# PIC32.net
KiCad netlist of a schematic drawn in Altium Designer
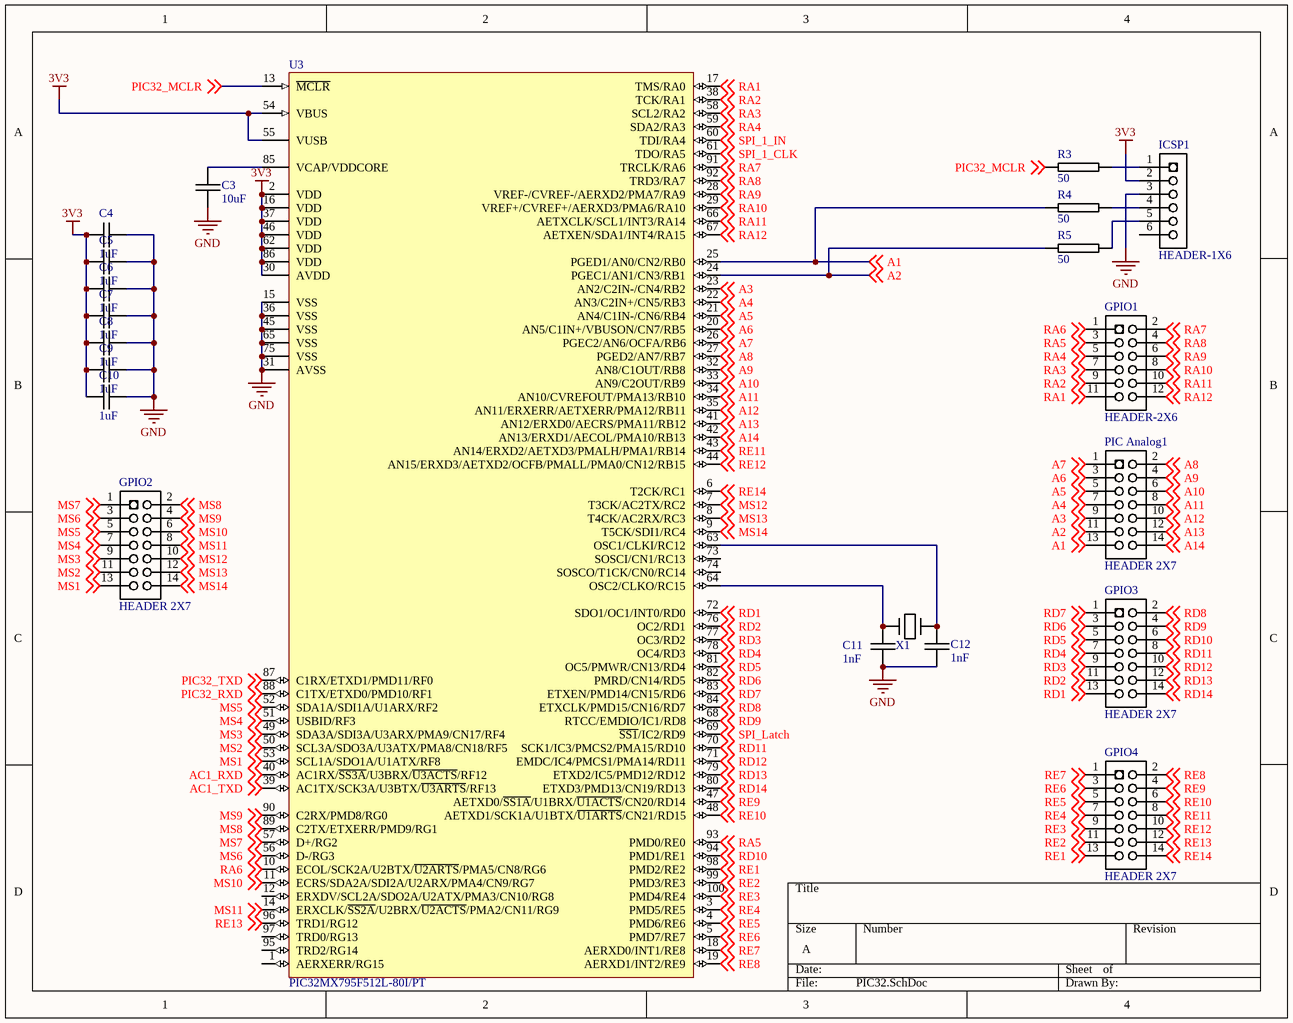
[diagram p0: PIC32.SchDoc]

(export (version "E")
  (design (tool "Eeschema 10.0.6"))
  (components
    (comp (ref "C3")
      (value "10uF")
      (footprint "0603C-GENERIC")
      (description "CAPACITOR 0603 CERAMIC")
      (fields
        (field (name "MANUFACTURER PART NUMBER") "GMK107BJ105KA-T")
        (field (name "MANUFACTURER") "Taiyo Yuden")
      )
      (libsource (lib "vh_altium_library") (part "0603C-1UF-35V-X5R-TAY"))
    )
    (comp (ref "C4")
      (value "1uF")
      (footprint "0603C-GENERIC")
      (description "CAPACITOR 0603 CERAMIC")
      (fields
        (field (name "MANUFACTURER PART NUMBER") "GMK107BJ105KA-T")
        (field (name "MANUFACTURER") "Taiyo Yuden")
      )
      (libsource (lib "vh_altium_library") (part "0603C-1UF-35V-X5R-TAY"))
    )
    (comp (ref "C5")
      (value "1uF")
      (footprint "0603C-GENERIC")
      (description "CAPACITOR 0603 CERAMIC")
      (fields
        (field (name "MANUFACTURER PART NUMBER") "GMK107BJ105KA-T")
        (field (name "MANUFACTURER") "Taiyo Yuden")
      )
      (libsource (lib "vh_altium_library") (part "0603C-1UF-35V-X5R-TAY"))
    )
    (comp (ref "C6")
      (value "1uF")
      (footprint "0603C-GENERIC")
      (description "CAPACITOR 0603 CERAMIC")
      (fields
        (field (name "MANUFACTURER PART NUMBER") "GMK107BJ105KA-T")
        (field (name "MANUFACTURER") "Taiyo Yuden")
      )
      (libsource (lib "vh_altium_library") (part "0603C-1UF-35V-X5R-TAY"))
    )
    (comp (ref "C7")
      (value "1uF")
      (footprint "0603C-GENERIC")
      (description "CAPACITOR 0603 CERAMIC")
      (fields
        (field (name "MANUFACTURER PART NUMBER") "GMK107BJ105KA-T")
        (field (name "MANUFACTURER") "Taiyo Yuden")
      )
      (libsource (lib "vh_altium_library") (part "0603C-1UF-35V-X5R-TAY"))
    )
    (comp (ref "C8")
      (value "1uF")
      (footprint "0603C-GENERIC")
      (description "CAPACITOR 0603 CERAMIC")
      (fields
        (field (name "MANUFACTURER PART NUMBER") "GMK107BJ105KA-T")
        (field (name "MANUFACTURER") "Taiyo Yuden")
      )
      (libsource (lib "vh_altium_library") (part "0603C-1UF-35V-X5R-TAY"))
    )
    (comp (ref "C9")
      (value "1uF")
      (footprint "0603C-GENERIC")
      (description "CAPACITOR 0603 CERAMIC")
      (fields
        (field (name "MANUFACTURER PART NUMBER") "GMK107BJ105KA-T")
        (field (name "MANUFACTURER") "Taiyo Yuden")
      )
      (libsource (lib "vh_altium_library") (part "0603C-1UF-35V-X5R-TAY"))
    )
    (comp (ref "C10")
      (value "1uF")
      (footprint "0603C-GENERIC")
      (description "CAPACITOR 0603 CERAMIC")
      (fields
        (field (name "MANUFACTURER PART NUMBER") "GMK107BJ105KA-T")
        (field (name "MANUFACTURER") "Taiyo Yuden")
      )
      (libsource (lib "vh_altium_library") (part "0603C-1UF-35V-X5R-TAY"))
    )
    (comp (ref "C11")
      (value "1nF")
      (footprint "0603C-GENERIC")
      (description "CAPACITOR 0603 CERAMIC")
      (libsource (lib "vh_altium_library") (part "0603C-000"))
    )
    (comp (ref "C12")
      (value "1nF")
      (footprint "0603C-GENERIC")
      (description "CAPACITOR 0603 CERAMIC")
      (libsource (lib "vh_altium_library") (part "0603C-000"))
    )
    (comp (ref "GPIO1")
      (value "HEADER-2X6")
      (footprint "HEADER-2X6")
      (libsource (lib "vh_altium_library") (part "HEADER-2X6"))
    )
    (comp (ref "GPIO2")
      (value "HEADER 2X7")
      (footprint "HEADER-2X7")
      (libsource (lib "vh_altium_library") (part "HEADER-2X7"))
    )
    (comp (ref "GPIO3")
      (value "HEADER 2X7")
      (footprint "HEADER-2X7")
      (libsource (lib "vh_altium_library") (part "HEADER-2X7"))
    )
    (comp (ref "GPIO4")
      (value "HEADER 2X7")
      (footprint "HEADER-2X7")
      (libsource (lib "vh_altium_library") (part "HEADER-2X7"))
    )
    (comp (ref "ICSP1")
      (value "HEADER-1X6")
      (footprint "HEADER-1X6")
      (libsource (lib "vh_altium_library") (part "HEADER-1X6"))
    )
    (comp (ref "PIC Analog1")
      (value "HEADER 2X7")
      (footprint "HEADER-2X7")
      (libsource (lib "vh_altium_library") (part "HEADER-2X7"))
    )
    (comp (ref "R3")
      (value "50")
      (footprint "0603R-TBD")
      (description "RESISTOR 0603 VALUE TO BE DETERMINED")
      (libsource (lib "vh_altium_library") (part "0603R-TBD"))
    )
    (comp (ref "R4")
      (value "50")
      (footprint "0603R-TBD")
      (description "RESISTOR 0603 VALUE TO BE DETERMINED")
      (libsource (lib "vh_altium_library") (part "0603R-TBD"))
    )
    (comp (ref "R5")
      (value "50")
      (footprint "0603R-TBD")
      (description "RESISTOR 0603 VALUE TO BE DETERMINED")
      (libsource (lib "vh_altium_library") (part "0603R-TBD"))
    )
    (comp (ref "U3")
      (value "PIC32MX795F512L-80I/PT")
      (footprint "TQFP-PT100_N")
      (fields (field (name "PUBLISHER") "Altium Limited"))
      (libsource (lib "Microchip Microcontroller 32-Bit PIC32") (part "PIC32MX795F512L-80I/PT"))
    )
    (comp (ref "X1")
      (value "CRYSTAL-GENERIC")
      (footprint "XTAL-RU49/4")
      (description "GENERIC CRYSTAL")
      (libsource (lib "vh_altium_library") (part "CRYSTAL-GENERIC"))
    )
  )
  (nets
    (net (code "1") (name "3V3") (class "Default")
      (node (ref "C10") (pin "1") (pintype "passive"))
      (node (ref "C4") (pin "1") (pintype "passive"))
      (node (ref "C5") (pin "1") (pintype "passive"))
      (node (ref "C6") (pin "1") (pintype "passive"))
      (node (ref "C7") (pin "1") (pintype "passive"))
      (node (ref "C8") (pin "1") (pintype "passive"))
      (node (ref "C9") (pin "1") (pintype "passive"))
      (node (ref "ICSP1") (pin "2") (pintype "passive"))
      (node (ref "U3") (pin "16") (pinfunction "VDD_16") (pintype "power_in"))
      (node (ref "U3") (pin "2") (pinfunction "VDD_2") (pintype "power_in"))
      (node (ref "U3") (pin "30") (pinfunction "AVDD_30") (pintype "power_in"))
      (node (ref "U3") (pin "37") (pinfunction "VDD_37") (pintype "power_in"))
      (node (ref "U3") (pin "46") (pinfunction "VDD_46") (pintype "power_in"))
      (node (ref "U3") (pin "54") (pinfunction "VBUS_54") (pintype "input"))
      (node (ref "U3") (pin "55") (pinfunction "VUSB_55") (pintype "power_in"))
      (node (ref "U3") (pin "62") (pinfunction "VDD_62") (pintype "power_in"))
      (node (ref "U3") (pin "86") (pinfunction "VDD_86") (pintype "power_in"))
    )
    (net (code "2") (name "A1") (class "Default")
      (node (ref "PIC Analog1") (pin "13") (pintype "passive"))
      (node (ref "R4") (pin "1") (pintype "passive"))
      (node (ref "U3") (pin "25") (pinfunction "PGED1/AN0/CN2/RB0_25") (pintype "bidirectional"))
    )
    (net (code "3") (name "A2") (class "Default")
      (node (ref "PIC Analog1") (pin "11") (pintype "passive"))
      (node (ref "R5") (pin "2") (pintype "passive"))
      (node (ref "U3") (pin "24") (pinfunction "PGEC1/AN1/CN3/RB1_24") (pintype "bidirectional"))
    )
    (net (code "4") (name "A3") (class "Default")
      (node (ref "PIC Analog1") (pin "9") (pintype "passive"))
      (node (ref "U3") (pin "23") (pinfunction "AN2/C2IN-/CN4/RB2_23") (pintype "bidirectional"))
    )
    (net (code "5") (name "A4") (class "Default")
      (node (ref "PIC Analog1") (pin "7") (pintype "passive"))
      (node (ref "U3") (pin "22") (pinfunction "AN3/C2IN+/CN5/RB3_22") (pintype "bidirectional"))
    )
    (net (code "6") (name "A5") (class "Default")
      (node (ref "PIC Analog1") (pin "5") (pintype "passive"))
      (node (ref "U3") (pin "21") (pinfunction "AN4/C1IN-/CN6/RB4_21") (pintype "bidirectional"))
    )
    (net (code "7") (name "A6") (class "Default")
      (node (ref "PIC Analog1") (pin "3") (pintype "passive"))
      (node (ref "U3") (pin "20") (pinfunction "AN5/C1IN+/VBUSON/CN7/RB5_20") (pintype "bidirectional"))
    )
    (net (code "8") (name "A7") (class "Default")
      (node (ref "PIC Analog1") (pin "1") (pintype "passive"))
      (node (ref "U3") (pin "26") (pinfunction "PGEC2/AN6/OCFA/RB6_26") (pintype "bidirectional"))
    )
    (net (code "9") (name "A8") (class "Default")
      (node (ref "PIC Analog1") (pin "2") (pintype "passive"))
      (node (ref "U3") (pin "27") (pinfunction "PGED2/AN7/RB7_27") (pintype "bidirectional"))
    )
    (net (code "10") (name "A9") (class "Default")
      (node (ref "PIC Analog1") (pin "4") (pintype "passive"))
      (node (ref "U3") (pin "32") (pinfunction "AN8/C1OUT/RB8_32") (pintype "bidirectional"))
    )
    (net (code "11") (name "A10") (class "Default")
      (node (ref "PIC Analog1") (pin "6") (pintype "passive"))
      (node (ref "U3") (pin "33") (pinfunction "AN9/C2OUT/RB9_33") (pintype "bidirectional"))
    )
    (net (code "12") (name "A11") (class "Default")
      (node (ref "PIC Analog1") (pin "8") (pintype "passive"))
      (node (ref "U3") (pin "34") (pinfunction "AN10/CVREFOUT/PMA13/RB10_34") (pintype "bidirectional"))
    )
    (net (code "13") (name "A12") (class "Default")
      (node (ref "PIC Analog1") (pin "10") (pintype "passive"))
      (node (ref "U3") (pin "35") (pinfunction "AN11/ERXERR/AETXERR/PMA12/RB11_35") (pintype "bidirectional"))
    )
    (net (code "14") (name "A13") (class "Default")
      (node (ref "PIC Analog1") (pin "12") (pintype "passive"))
      (node (ref "U3") (pin "41") (pinfunction "AN12/ERXD0/AECRS/PMA11/RB12_41") (pintype "bidirectional"))
    )
    (net (code "15") (name "A14") (class "Default")
      (node (ref "PIC Analog1") (pin "14") (pintype "passive"))
      (node (ref "U3") (pin "42") (pinfunction "AN13/ERXD1/AECOL/PMA10/RB13_42") (pintype "bidirectional"))
    )
    (net (code "16") (name "AC1_RXD") (class "Default")
      (node (ref "U3") (pin "40") (pinfunction "AC1RX/~{SS3A}/U3BRX/~{U3ACTS}/RF12_40") (pintype "bidirectional"))
    )
    (net (code "17") (name "AC1_TXD") (class "Default")
      (node (ref "U3") (pin "39") (pinfunction "AC1TX/SCK3A/U3BTX/~{U3ARTS}/RF13_39") (pintype "bidirectional"))
    )
    (net (code "18") (name "GND") (class "Default")
      (node (ref "C10") (pin "2") (pintype "passive"))
      (node (ref "C11") (pin "2") (pintype "passive"))
      (node (ref "C12") (pin "2") (pintype "passive"))
      (node (ref "C3") (pin "2") (pintype "passive"))
      (node (ref "C4") (pin "2") (pintype "passive"))
      (node (ref "C5") (pin "2") (pintype "passive"))
      (node (ref "C6") (pin "2") (pintype "passive"))
      (node (ref "C7") (pin "2") (pintype "passive"))
      (node (ref "C8") (pin "2") (pintype "passive"))
      (node (ref "C9") (pin "2") (pintype "passive"))
      (node (ref "ICSP1") (pin "3") (pintype "passive"))
      (node (ref "U3") (pin "15") (pinfunction "VSS_15") (pintype "power_in"))
      (node (ref "U3") (pin "31") (pinfunction "AVSS_31") (pintype "power_in"))
      (node (ref "U3") (pin "36") (pinfunction "VSS_36") (pintype "power_in"))
      (node (ref "U3") (pin "45") (pinfunction "VSS_45") (pintype "power_in"))
      (node (ref "U3") (pin "65") (pinfunction "VSS_65") (pintype "power_in"))
      (node (ref "U3") (pin "75") (pinfunction "VSS_75") (pintype "power_in"))
    )
    (net (code "19") (name "MS1") (class "Default")
      (node (ref "GPIO2") (pin "13") (pintype "passive"))
      (node (ref "U3") (pin "53") (pinfunction "SCL1A/SDO1A/U1ATX/RF8_53") (pintype "bidirectional"))
    )
    (net (code "20") (name "MS2") (class "Default")
      (node (ref "GPIO2") (pin "11") (pintype "passive"))
      (node (ref "U3") (pin "50") (pinfunction "SCL3A/SDO3A/U3ATX/PMA8/CN18/RF5_50") (pintype "bidirectional"))
    )
    (net (code "21") (name "MS3") (class "Default")
      (node (ref "GPIO2") (pin "9") (pintype "passive"))
      (node (ref "U3") (pin "49") (pinfunction "SDA3A/SDI3A/U3ARX/PMA9/CN17/RF4_49") (pintype "bidirectional"))
    )
    (net (code "22") (name "MS4") (class "Default")
      (node (ref "GPIO2") (pin "7") (pintype "passive"))
      (node (ref "U3") (pin "51") (pinfunction "USBID/RF3_51") (pintype "bidirectional"))
    )
    (net (code "23") (name "MS5") (class "Default")
      (node (ref "GPIO2") (pin "5") (pintype "passive"))
      (node (ref "U3") (pin "52") (pinfunction "SDA1A/SDI1A/U1ARX/RF2_52") (pintype "bidirectional"))
    )
    (net (code "24") (name "MS6") (class "Default")
      (node (ref "GPIO2") (pin "3") (pintype "passive"))
      (node (ref "U3") (pin "56") (pinfunction "D-/RG3_56") (pintype "bidirectional"))
    )
    (net (code "25") (name "MS7") (class "Default")
      (node (ref "GPIO2") (pin "1") (pintype "passive"))
      (node (ref "U3") (pin "57") (pinfunction "D+/RG2_57") (pintype "bidirectional"))
    )
    (net (code "26") (name "MS8") (class "Default")
      (node (ref "GPIO2") (pin "2") (pintype "passive"))
      (node (ref "U3") (pin "89") (pinfunction "C2TX/ETXERR/PMD9/RG1_89") (pintype "bidirectional"))
    )
    (net (code "27") (name "MS9") (class "Default")
      (node (ref "GPIO2") (pin "4") (pintype "passive"))
      (node (ref "U3") (pin "90") (pinfunction "C2RX/PMD8/RG0_90") (pintype "bidirectional"))
    )
    (net (code "28") (name "MS10") (class "Default")
      (node (ref "GPIO2") (pin "6") (pintype "passive"))
      (node (ref "U3") (pin "11") (pinfunction "ECRS/SDA2A/SDI2A/U2ARX/PMA4/CN9/RG7_11") (pintype "bidirectional"))
    )
    (net (code "29") (name "MS11") (class "Default")
      (node (ref "GPIO2") (pin "8") (pintype "passive"))
      (node (ref "U3") (pin "14") (pinfunction "ERXCLK/~{SS2A}/U2BRX/~{U2ACTS}/PMA2/CN11/RG9_14") (pintype "bidirectional"))
    )
    (net (code "30") (name "MS12") (class "Default")
      (node (ref "GPIO2") (pin "10") (pintype "passive"))
      (node (ref "U3") (pin "7") (pinfunction "T3CK/AC2TX/RC2_7") (pintype "bidirectional"))
    )
    (net (code "31") (name "MS13") (class "Default")
      (node (ref "GPIO2") (pin "12") (pintype "passive"))
      (node (ref "U3") (pin "8") (pinfunction "T4CK/AC2RX/RC3_8") (pintype "bidirectional"))
    )
    (net (code "32") (name "MS14") (class "Default")
      (node (ref "GPIO2") (pin "14") (pintype "passive"))
      (node (ref "U3") (pin "9") (pinfunction "T5CK/SDI1/RC4_9") (pintype "bidirectional"))
    )
    (net (code "33") (name "Net-(ICSP1-Pad1)") (class "Default")
      (node (ref "ICSP1") (pin "1") (pintype "passive"))
      (node (ref "R3") (pin "1") (pintype "passive"))
    )
    (net (code "34") (name "Net-(ICSP1-Pad4)") (class "Default")
      (node (ref "ICSP1") (pin "4") (pintype "passive"))
      (node (ref "R4") (pin "2") (pintype "passive"))
    )
    (net (code "35") (name "Net-(ICSP1-Pad5)") (class "Default")
      (node (ref "ICSP1") (pin "5") (pintype "passive"))
      (node (ref "R5") (pin "1") (pintype "passive"))
    )
    (net (code "36") (name "Net-(U3-OSC1{slash}CLKI{slash}RC12)") (class "Default")
      (node (ref "C12") (pin "1") (pintype "passive"))
      (node (ref "U3") (pin "63") (pinfunction "OSC1/CLKI/RC12_63") (pintype "bidirectional"))
      (node (ref "X1") (pin "2") (pintype "passive"))
    )
    (net (code "37") (name "Net-(U3-OSC2{slash}CLKO{slash}RC15)") (class "Default")
      (node (ref "C11") (pin "1") (pintype "passive"))
      (node (ref "U3") (pin "64") (pinfunction "OSC2/CLKO/RC15_64") (pintype "bidirectional"))
      (node (ref "X1") (pin "1") (pintype "passive"))
    )
    (net (code "38") (name "Net-(U3-VCAP{slash}VDDCORE)") (class "Default")
      (node (ref "C3") (pin "1") (pintype "passive"))
      (node (ref "U3") (pin "85") (pinfunction "VCAP/VDDCORE_85") (pintype "power_in"))
    )
    (net (code "39") (name "PIC32_MCLR") (class "Default")
      (node (ref "R3") (pin "2") (pintype "passive"))
      (node (ref "U3") (pin "13") (pinfunction "~{MCLR}_13") (pintype "input"))
    )
    (net (code "40") (name "PIC32_RXD") (class "Default")
      (node (ref "U3") (pin "88") (pinfunction "C1TX/ETXD0/PMD10/RF1_88") (pintype "bidirectional"))
    )
    (net (code "41") (name "PIC32_TXD") (class "Default")
      (node (ref "U3") (pin "87") (pinfunction "C1RX/ETXD1/PMD11/RF0_87") (pintype "bidirectional"))
    )
    (net (code "42") (name "RA1") (class "Default")
      (node (ref "GPIO1") (pin "11") (pintype "passive"))
      (node (ref "U3") (pin "17") (pinfunction "TMS/RA0_17") (pintype "bidirectional"))
    )
    (net (code "43") (name "RA2") (class "Default")
      (node (ref "GPIO1") (pin "9") (pintype "passive"))
      (node (ref "U3") (pin "38") (pinfunction "TCK/RA1_38") (pintype "bidirectional"))
    )
    (net (code "44") (name "RA3") (class "Default")
      (node (ref "GPIO1") (pin "7") (pintype "passive"))
      (node (ref "U3") (pin "58") (pinfunction "SCL2/RA2_58") (pintype "bidirectional"))
    )
    (net (code "45") (name "RA4") (class "Default")
      (node (ref "GPIO1") (pin "5") (pintype "passive"))
      (node (ref "U3") (pin "59") (pinfunction "SDA2/RA3_59") (pintype "bidirectional"))
    )
    (net (code "46") (name "RA5") (class "Default")
      (node (ref "GPIO1") (pin "3") (pintype "passive"))
      (node (ref "U3") (pin "93") (pinfunction "PMD0/RE0_93") (pintype "bidirectional"))
    )
    (net (code "47") (name "RA6") (class "Default")
      (node (ref "GPIO1") (pin "1") (pintype "passive"))
      (node (ref "U3") (pin "10") (pinfunction "ECOL/SCK2A/U2BTX/~{U2ARTS}/PMA5/CN8/RG6_10") (pintype "bidirectional"))
    )
    (net (code "48") (name "RA7") (class "Default")
      (node (ref "GPIO1") (pin "2") (pintype "passive"))
      (node (ref "U3") (pin "91") (pinfunction "TRCLK/RA6_91") (pintype "bidirectional"))
    )
    (net (code "49") (name "RA8") (class "Default")
      (node (ref "GPIO1") (pin "4") (pintype "passive"))
      (node (ref "U3") (pin "92") (pinfunction "TRD3/RA7_92") (pintype "bidirectional"))
    )
    (net (code "50") (name "RA9") (class "Default")
      (node (ref "GPIO1") (pin "6") (pintype "passive"))
      (node (ref "U3") (pin "28") (pinfunction "VREF-/CVREF-/AERXD2/PMA7/RA9_28") (pintype "bidirectional"))
    )
    (net (code "51") (name "RA10") (class "Default")
      (node (ref "GPIO1") (pin "8") (pintype "passive"))
      (node (ref "U3") (pin "29") (pinfunction "VREF+/CVREF+/AERXD3/PMA6/RA10_29") (pintype "bidirectional"))
    )
    (net (code "52") (name "RA11") (class "Default")
      (node (ref "GPIO1") (pin "10") (pintype "passive"))
      (node (ref "U3") (pin "66") (pinfunction "AETXCLK/SCL1/INT3/RA14_66") (pintype "bidirectional"))
    )
    (net (code "53") (name "RA12") (class "Default")
      (node (ref "GPIO1") (pin "12") (pintype "passive"))
      (node (ref "U3") (pin "67") (pinfunction "AETXEN/SDA1/INT4/RA15_67") (pintype "bidirectional"))
    )
    (net (code "54") (name "RD1") (class "Default")
      (node (ref "GPIO3") (pin "13") (pintype "passive"))
      (node (ref "U3") (pin "72") (pinfunction "SDO1/OC1/INT0/RD0_72") (pintype "bidirectional"))
    )
    (net (code "55") (name "RD2") (class "Default")
      (node (ref "GPIO3") (pin "11") (pintype "passive"))
      (node (ref "U3") (pin "76") (pinfunction "OC2/RD1_76") (pintype "bidirectional"))
    )
    (net (code "56") (name "RD3") (class "Default")
      (node (ref "GPIO3") (pin "9") (pintype "passive"))
      (node (ref "U3") (pin "77") (pinfunction "OC3/RD2_77") (pintype "bidirectional"))
    )
    (net (code "57") (name "RD4") (class "Default")
      (node (ref "GPIO3") (pin "7") (pintype "passive"))
      (node (ref "U3") (pin "78") (pinfunction "OC4/RD3_78") (pintype "bidirectional"))
    )
    (net (code "58") (name "RD5") (class "Default")
      (node (ref "GPIO3") (pin "5") (pintype "passive"))
      (node (ref "U3") (pin "81") (pinfunction "OC5/PMWR/CN13/RD4_81") (pintype "bidirectional"))
    )
    (net (code "59") (name "RD6") (class "Default")
      (node (ref "GPIO3") (pin "3") (pintype "passive"))
      (node (ref "U3") (pin "82") (pinfunction "PMRD/CN14/RD5_82") (pintype "bidirectional"))
    )
    (net (code "60") (name "RD7") (class "Default")
      (node (ref "GPIO3") (pin "1") (pintype "passive"))
      (node (ref "U3") (pin "83") (pinfunction "ETXEN/PMD14/CN15/RD6_83") (pintype "bidirectional"))
    )
    (net (code "61") (name "RD8") (class "Default")
      (node (ref "GPIO3") (pin "2") (pintype "passive"))
      (node (ref "U3") (pin "84") (pinfunction "ETXCLK/PMD15/CN16/RD7_84") (pintype "bidirectional"))
    )
    (net (code "62") (name "RD9") (class "Default")
      (node (ref "GPIO3") (pin "4") (pintype "passive"))
      (node (ref "U3") (pin "68") (pinfunction "RTCC/EMDIO/IC1/RD8_68") (pintype "bidirectional"))
    )
    (net (code "63") (name "RD10") (class "Default")
      (node (ref "GPIO3") (pin "6") (pintype "passive"))
      (node (ref "U3") (pin "94") (pinfunction "PMD1/RE1_94") (pintype "bidirectional"))
    )
    (net (code "64") (name "RD11") (class "Default")
      (node (ref "GPIO3") (pin "8") (pintype "passive"))
      (node (ref "U3") (pin "70") (pinfunction "SCK1/IC3/PMCS2/PMA15/RD10_70") (pintype "bidirectional"))
    )
    (net (code "65") (name "RD12") (class "Default")
      (node (ref "GPIO3") (pin "10") (pintype "passive"))
      (node (ref "U3") (pin "71") (pinfunction "EMDC/IC4/PMCS1/PMA14/RD11_71") (pintype "bidirectional"))
    )
    (net (code "66") (name "RD13") (class "Default")
      (node (ref "GPIO3") (pin "12") (pintype "passive"))
      (node (ref "U3") (pin "79") (pinfunction "ETXD2/IC5/PMD12/RD12_79") (pintype "bidirectional"))
    )
    (net (code "67") (name "RD14") (class "Default")
      (node (ref "GPIO3") (pin "14") (pintype "passive"))
      (node (ref "U3") (pin "80") (pinfunction "ETXD3/PMD13/CN19/RD13_80") (pintype "bidirectional"))
    )
    (net (code "68") (name "RE1") (class "Default")
      (node (ref "GPIO4") (pin "13") (pintype "passive"))
      (node (ref "U3") (pin "98") (pinfunction "PMD2/RE2_98") (pintype "bidirectional"))
    )
    (net (code "69") (name "RE2") (class "Default")
      (node (ref "GPIO4") (pin "11") (pintype "passive"))
      (node (ref "U3") (pin "99") (pinfunction "PMD3/RE3_99") (pintype "bidirectional"))
    )
    (net (code "70") (name "RE3") (class "Default")
      (node (ref "GPIO4") (pin "9") (pintype "passive"))
      (node (ref "U3") (pin "100") (pinfunction "PMD4/RE4_100") (pintype "bidirectional"))
    )
    (net (code "71") (name "RE4") (class "Default")
      (node (ref "GPIO4") (pin "7") (pintype "passive"))
      (node (ref "U3") (pin "3") (pinfunction "PMD5/RE5_3") (pintype "bidirectional"))
    )
    (net (code "72") (name "RE5") (class "Default")
      (node (ref "GPIO4") (pin "5") (pintype "passive"))
      (node (ref "U3") (pin "4") (pinfunction "PMD6/RE6_4") (pintype "bidirectional"))
    )
    (net (code "73") (name "RE6") (class "Default")
      (node (ref "GPIO4") (pin "3") (pintype "passive"))
      (node (ref "U3") (pin "5") (pinfunction "PMD7/RE7_5") (pintype "bidirectional"))
    )
    (net (code "74") (name "RE7") (class "Default")
      (node (ref "GPIO4") (pin "1") (pintype "passive"))
      (node (ref "U3") (pin "18") (pinfunction "AERXD0/INT1/RE8_18") (pintype "bidirectional"))
    )
    (net (code "75") (name "RE8") (class "Default")
      (node (ref "GPIO4") (pin "2") (pintype "passive"))
      (node (ref "U3") (pin "19") (pinfunction "AERXD1/INT2/RE9_19") (pintype "bidirectional"))
    )
    (net (code "76") (name "RE9") (class "Default")
      (node (ref "GPIO4") (pin "4") (pintype "passive"))
      (node (ref "U3") (pin "47") (pinfunction "AETXD0/~{SS1A}/U1BRX/~{U1ACTS}/CN20/RD14_47") (pintype "bidirectional"))
    )
    (net (code "77") (name "RE10") (class "Default")
      (node (ref "GPIO4") (pin "6") (pintype "passive"))
      (node (ref "U3") (pin "48") (pinfunction "AETXD1/SCK1A/U1BTX/~{U1ARTS}/CN21/RD15_48") (pintype "bidirectional"))
    )
    (net (code "78") (name "RE11") (class "Default")
      (node (ref "GPIO4") (pin "8") (pintype "passive"))
      (node (ref "U3") (pin "43") (pinfunction "AN14/ERXD2/AETXD3/PMALH/PMA1/RB14_43") (pintype "bidirectional"))
    )
    (net (code "79") (name "RE12") (class "Default")
      (node (ref "GPIO4") (pin "10") (pintype "passive"))
      (node (ref "U3") (pin "44") (pinfunction "AN15/ERXD3/AETXD2/OCFB/PMALL/PMA0/CN12/RB15_44") (pintype "bidirectional"))
    )
    (net (code "80") (name "RE13") (class "Default")
      (node (ref "GPIO4") (pin "12") (pintype "passive"))
      (node (ref "U3") (pin "96") (pinfunction "TRD1/RG12_96") (pintype "bidirectional"))
    )
    (net (code "81") (name "RE14") (class "Default")
      (node (ref "GPIO4") (pin "14") (pintype "passive"))
      (node (ref "U3") (pin "6") (pinfunction "T2CK/RC1_6") (pintype "bidirectional"))
    )
    (net (code "82") (name "SPI_1_CLK") (class "Default")
      (node (ref "U3") (pin "61") (pinfunction "TDO/RA5_61") (pintype "bidirectional"))
    )
    (net (code "83") (name "SPI_1_IN") (class "Default")
      (node (ref "U3") (pin "60") (pinfunction "TDI/RA4_60") (pintype "bidirectional"))
    )
    (net (code "84") (name "SPI_Latch") (class "Default")
      (node (ref "U3") (pin "69") (pinfunction "~{SS1}/IC2/RD9_69") (pintype "bidirectional"))
    )
    (net (code "85") (name "unconnected-(ICSP1-Pad6)") (class "Default")
      (node (ref "ICSP1") (pin "6") (pintype "passive"))
    )
    (net (code "86") (name "unconnected-(U3-AERXERR{slash}RG15-Pad1)") (class "Default")
      (node (ref "U3") (pin "1") (pinfunction "AERXERR/RG15_1") (pintype "bidirectional"))
    )
    (net (code "87") (name "unconnected-(U3-ERXDV{slash}SCL2A{slash}SDO2A{slash}U2ATX{slash}PMA3{slash}CN10{slash}RG8-Pad12)") (class "Default")
      (node (ref "U3") (pin "12") (pinfunction "ERXDV/SCL2A/SDO2A/U2ATX/PMA3/CN10/RG8_12") (pintype "bidirectional"))
    )
    (net (code "88") (name "unconnected-(U3-SOSCI{slash}CN1{slash}RC13-Pad73)") (class "Default")
      (node (ref "U3") (pin "73") (pinfunction "SOSCI/CN1/RC13_73") (pintype "bidirectional"))
    )
    (net (code "89") (name "unconnected-(U3-SOSCO{slash}T1CK{slash}CN0{slash}RC14-Pad74)") (class "Default")
      (node (ref "U3") (pin "74") (pinfunction "SOSCO/T1CK/CN0/RC14_74") (pintype "bidirectional"))
    )
    (net (code "90") (name "unconnected-(U3-TRD0{slash}RG13-Pad97)") (class "Default")
      (node (ref "U3") (pin "97") (pinfunction "TRD0/RG13_97") (pintype "bidirectional"))
    )
    (net (code "91") (name "unconnected-(U3-TRD2{slash}RG14-Pad95)") (class "Default")
      (node (ref "U3") (pin "95") (pinfunction "TRD2/RG14_95") (pintype "bidirectional"))
    )
  )
)
